# DC_Link_Non-Isolated.net
KiCad netlist of a schematic drawn in Altium Designer
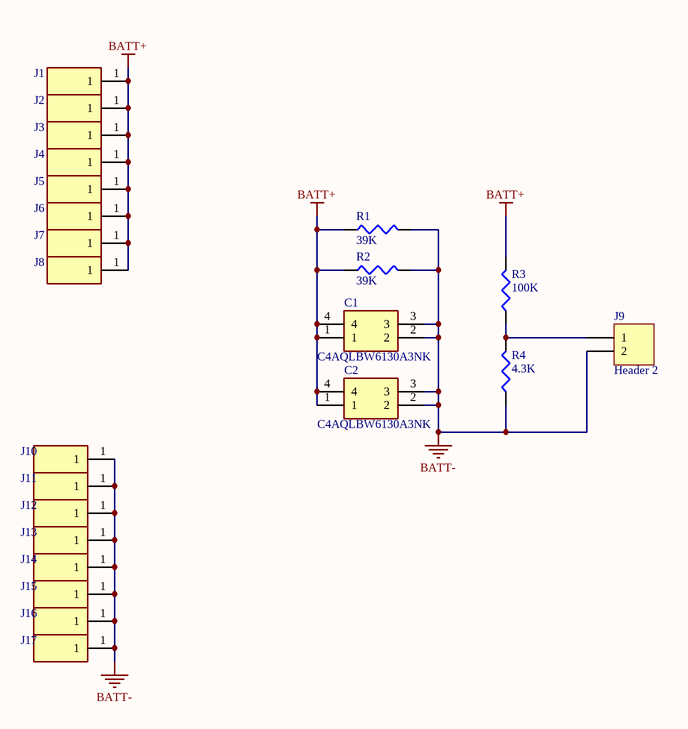
[diagram p0: DC Link Non-Isolated.SchDoc]

(export (version "E")
  (design (tool "Eeschema 10.0.6"))
  (components
    (comp (ref "C1")
      (value "C4AQLBW6130A3NK")
      (footprint "Motor Controller:C4AQLBW6130A3NK")
      (description "Capacitor")
      (libsource (lib "Motor Controller") (part "C4AQLBW6130A3NK"))
    )
    (comp (ref "C2")
      (value "C4AQLBW6130A3NK")
      (footprint "Motor Controller:C4AQLBW6130A3NK")
      (description "Capacitor")
      (libsource (lib "Motor Controller") (part "C4AQLBW6130A3NK"))
    )
    (comp (ref "J1")
      (value "8730")
      (footprint "Motor Controller:8730")
      (description "Connector")
      (fields (field (name "MOUSER PART NUMBER") "534-8730"))
      (libsource (lib "Motor Controller") (part "8730"))
    )
    (comp (ref "J2")
      (value "8730")
      (footprint "Motor Controller:8730")
      (description "Connector")
      (fields (field (name "MOUSER PART NUMBER") "534-8730"))
      (libsource (lib "Motor Controller") (part "8730"))
    )
    (comp (ref "J3")
      (value "8730")
      (footprint "Motor Controller:8730")
      (description "Connector")
      (fields (field (name "MOUSER PART NUMBER") "534-8730"))
      (libsource (lib "Motor Controller") (part "8730"))
    )
    (comp (ref "J4")
      (value "8730")
      (footprint "Motor Controller:8730")
      (description "Connector")
      (fields (field (name "MOUSER PART NUMBER") "534-8730"))
      (libsource (lib "Motor Controller") (part "8730"))
    )
    (comp (ref "J5")
      (value "8730")
      (footprint "Motor Controller:8730")
      (description "Connector")
      (fields (field (name "MOUSER PART NUMBER") "534-8730"))
      (libsource (lib "Motor Controller") (part "8730"))
    )
    (comp (ref "J6")
      (value "8730")
      (footprint "Motor Controller:8730")
      (description "Connector")
      (fields (field (name "MOUSER PART NUMBER") "534-8730"))
      (libsource (lib "Motor Controller") (part "8730"))
    )
    (comp (ref "J7")
      (value "8730")
      (footprint "Motor Controller:8730")
      (description "Connector")
      (fields (field (name "MOUSER PART NUMBER") "534-8730"))
      (libsource (lib "Motor Controller") (part "8730"))
    )
    (comp (ref "J8")
      (value "8730")
      (footprint "Motor Controller:8730")
      (description "Connector")
      (fields (field (name "MOUSER PART NUMBER") "534-8730"))
      (libsource (lib "Motor Controller") (part "8730"))
    )
    (comp (ref "J9")
      (value "Header 2")
      (footprint "HDR1X2")
      (description "Header, 2-Pin")
      (fields (field (name "PUBLISHER") "Altium Limited"))
      (libsource (lib "Miscellaneous Connectors") (part "Header 2"))
    )
    (comp (ref "J10")
      (value "8730")
      (footprint "Motor Controller:8730")
      (description "Connector")
      (fields (field (name "MOUSER PART NUMBER") "534-8730"))
      (libsource (lib "Motor Controller") (part "8730"))
    )
    (comp (ref "J11")
      (value "8730")
      (footprint "Motor Controller:8730")
      (description "Connector")
      (fields (field (name "MOUSER PART NUMBER") "534-8730"))
      (libsource (lib "Motor Controller") (part "8730"))
    )
    (comp (ref "J12")
      (value "8730")
      (footprint "Motor Controller:8730")
      (description "Connector")
      (fields (field (name "MOUSER PART NUMBER") "534-8730"))
      (libsource (lib "Motor Controller") (part "8730"))
    )
    (comp (ref "J13")
      (value "8730")
      (footprint "Motor Controller:8730")
      (description "Connector")
      (fields (field (name "MOUSER PART NUMBER") "534-8730"))
      (libsource (lib "Motor Controller") (part "8730"))
    )
    (comp (ref "J14")
      (value "8730")
      (footprint "Motor Controller:8730")
      (description "Connector")
      (fields (field (name "MOUSER PART NUMBER") "534-8730"))
      (libsource (lib "Motor Controller") (part "8730"))
    )
    (comp (ref "J15")
      (value "8730")
      (footprint "Motor Controller:8730")
      (description "Connector")
      (fields (field (name "MOUSER PART NUMBER") "534-8730"))
      (libsource (lib "Motor Controller") (part "8730"))
    )
    (comp (ref "J16")
      (value "8730")
      (footprint "Motor Controller:8730")
      (description "Connector")
      (fields (field (name "MOUSER PART NUMBER") "534-8730"))
      (libsource (lib "Motor Controller") (part "8730"))
    )
    (comp (ref "J17")
      (value "8730")
      (footprint "Motor Controller:8730")
      (description "Connector")
      (fields (field (name "MOUSER PART NUMBER") "534-8730"))
      (libsource (lib "Motor Controller") (part "8730"))
    )
    (comp (ref "R1")
      (value "39K")
      (footprint "C1206")
      (description "Resistor")
      (fields (field (name "Comment") "Res3") (field (name "PUBLISHER") "Altium Limited"))
      (libsource (lib "Miscellaneous Devices") (part "Res3"))
    )
    (comp (ref "R2")
      (value "39K")
      (footprint "C1206")
      (description "Resistor")
      (fields (field (name "Comment") "Res3") (field (name "PUBLISHER") "Altium Limited"))
      (libsource (lib "Miscellaneous Devices") (part "Res3"))
    )
    (comp (ref "R3")
      (value "100K")
      (footprint "J1-0603")
      (description "Resistor")
      (fields (field (name "Comment") "Res3") (field (name "PUBLISHER") "Altium Limited"))
      (libsource (lib "Miscellaneous Devices") (part "Res3"))
    )
    (comp (ref "R4")
      (value "4.3K")
      (footprint "J1-0603")
      (description "Resistor")
      (fields (field (name "Comment") "Res3") (field (name "PUBLISHER") "Altium Limited"))
      (libsource (lib "Miscellaneous Devices") (part "Res3"))
    )
  )
  (nets
    (net (code "1") (name "BATT+") (class "Default")
      (node (ref "C1") (pin "1") (pinfunction "1_1") (pintype "passive"))
      (node (ref "C1") (pin "4") (pinfunction "4_4") (pintype "passive"))
      (node (ref "C2") (pin "1") (pinfunction "1_1") (pintype "passive"))
      (node (ref "C2") (pin "4") (pinfunction "4_4") (pintype "passive"))
      (node (ref "J1") (pin "1") (pinfunction "1_1") (pintype "passive"))
      (node (ref "J2") (pin "1") (pinfunction "1_1") (pintype "passive"))
      (node (ref "J3") (pin "1") (pinfunction "1_1") (pintype "passive"))
      (node (ref "J4") (pin "1") (pinfunction "1_1") (pintype "passive"))
      (node (ref "J5") (pin "1") (pinfunction "1_1") (pintype "passive"))
      (node (ref "J6") (pin "1") (pinfunction "1_1") (pintype "passive"))
      (node (ref "J7") (pin "1") (pinfunction "1_1") (pintype "passive"))
      (node (ref "J8") (pin "1") (pinfunction "1_1") (pintype "passive"))
      (node (ref "R1") (pin "1") (pinfunction "1_1") (pintype "passive"))
      (node (ref "R2") (pin "1") (pinfunction "1_1") (pintype "passive"))
      (node (ref "R3") (pin "2") (pinfunction "2_2") (pintype "passive"))
    )
    (net (code "2") (name "BATT-") (class "Default")
      (node (ref "C1") (pin "2") (pinfunction "2_2") (pintype "passive"))
      (node (ref "C1") (pin "3") (pinfunction "3_3") (pintype "passive"))
      (node (ref "C2") (pin "2") (pinfunction "2_2") (pintype "passive"))
      (node (ref "C2") (pin "3") (pinfunction "3_3") (pintype "passive"))
      (node (ref "J10") (pin "1") (pinfunction "1_1") (pintype "passive"))
      (node (ref "J11") (pin "1") (pinfunction "1_1") (pintype "passive"))
      (node (ref "J12") (pin "1") (pinfunction "1_1") (pintype "passive"))
      (node (ref "J13") (pin "1") (pinfunction "1_1") (pintype "passive"))
      (node (ref "J14") (pin "1") (pinfunction "1_1") (pintype "passive"))
      (node (ref "J15") (pin "1") (pinfunction "1_1") (pintype "passive"))
      (node (ref "J16") (pin "1") (pinfunction "1_1") (pintype "passive"))
      (node (ref "J17") (pin "1") (pinfunction "1_1") (pintype "passive"))
      (node (ref "J9") (pin "2") (pinfunction "2_2") (pintype "passive"))
      (node (ref "R1") (pin "2") (pinfunction "2_2") (pintype "passive"))
      (node (ref "R2") (pin "2") (pinfunction "2_2") (pintype "passive"))
      (node (ref "R4") (pin "1") (pinfunction "1_1") (pintype "passive"))
    )
    (net (code "3") (name "Net-(J9-Pad1)") (class "Default")
      (node (ref "J9") (pin "1") (pinfunction "1_1") (pintype "passive"))
      (node (ref "R3") (pin "1") (pinfunction "1_1") (pintype "passive"))
      (node (ref "R4") (pin "2") (pinfunction "2_2") (pintype "passive"))
    )
  )
)
